# Clock-Gen.net
KiCad netlist of a schematic drawn in Altium Designer
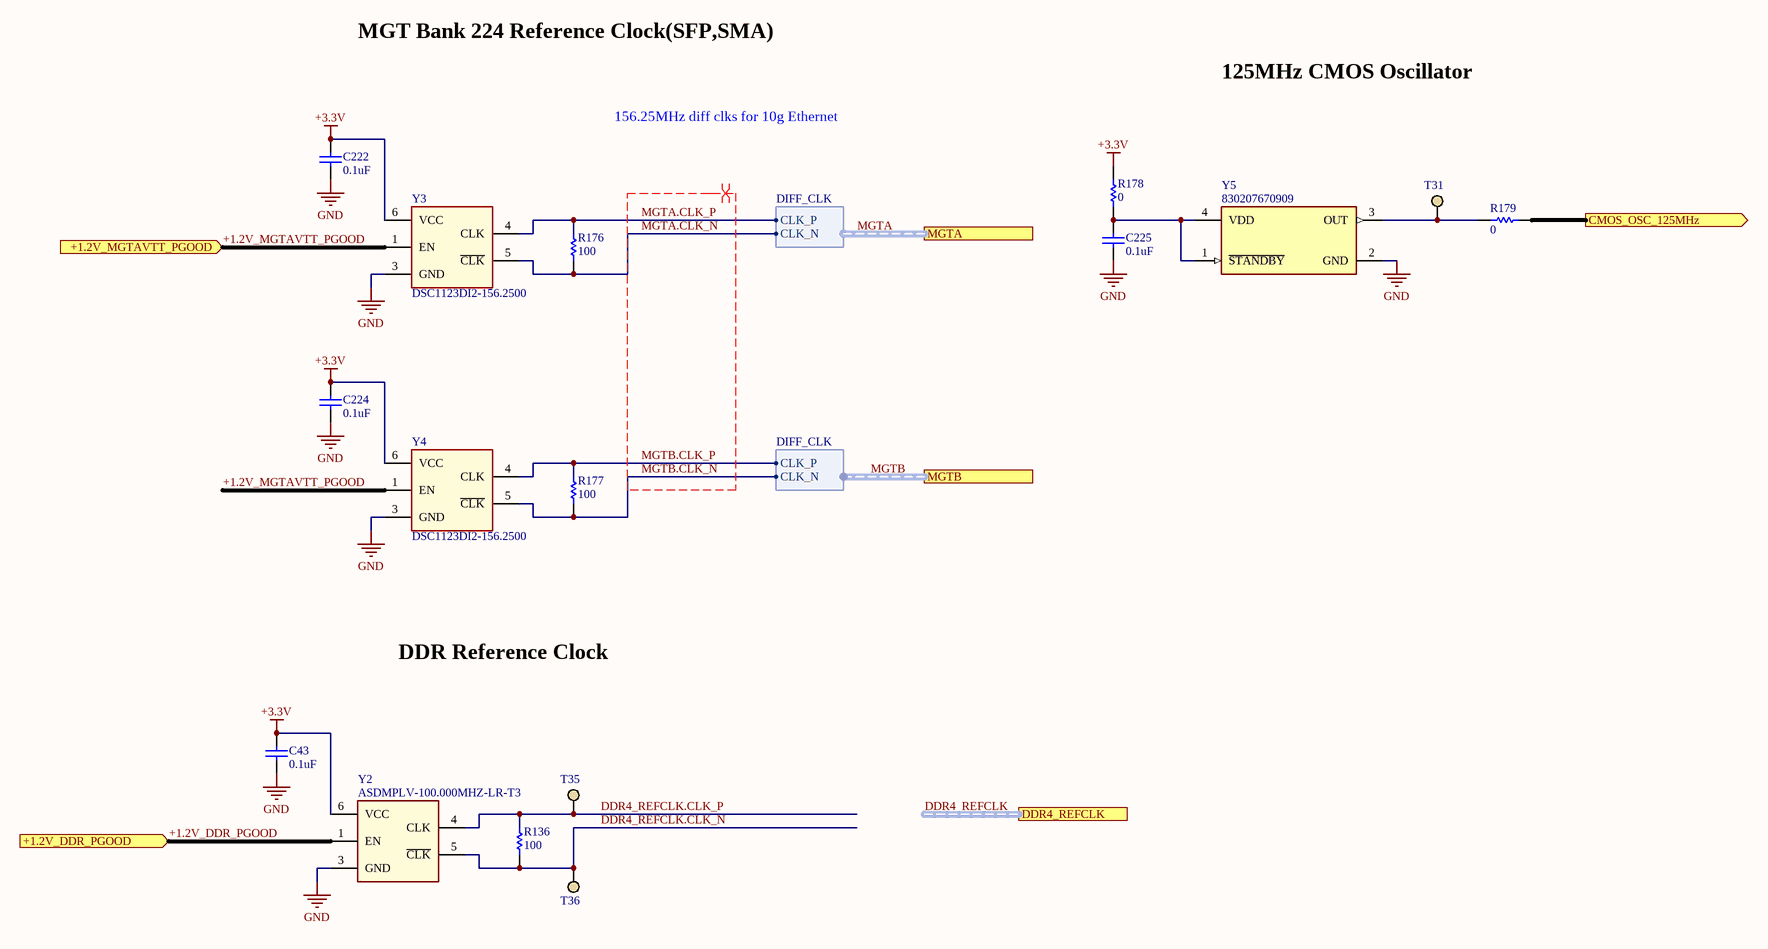
[diagram p0: Clock-Gen.SchDoc]

(export (version "E")
  (design (tool "Eeschema 10.0.6"))
  (components
    (comp (ref "C43")
      (value "0.1uF")
      (footprint "CAPC1005X55USR")
      (description "CAP CER 0.1UF 25V X5R 0402")
      (fields
        (field (name "MANUFACTURER PART NUMBER") "CL05A104KA5NNNC")
        (field (name "MANUFACTURER") "Samsung Electro-Mechanics")
      )
      (libsource (lib "Radar FPGA RF") (part "CAP CER 0.1UF 25V X5R 0402"))
    )
    (comp (ref "C222")
      (value "0.1uF")
      (footprint "CAPC1005X55USR")
      (description "CAP CER 0.1UF 25V X5R 0402")
      (fields
        (field (name "MANUFACTURER PART NUMBER") "CL05A104KA5NNNC")
        (field (name "MANUFACTURER") "Samsung Electro-Mechanics")
      )
      (libsource (lib "Radar FPGA RF") (part "CAP CER 0.1UF 25V X5R 0402"))
    )
    (comp (ref "C224")
      (value "0.1uF")
      (footprint "CAPC1005X55USR")
      (description "CAP CER 0.1UF 25V X5R 0402")
      (fields
        (field (name "MANUFACTURER PART NUMBER") "CL05A104KA5NNNC")
        (field (name "MANUFACTURER") "Samsung Electro-Mechanics")
      )
      (libsource (lib "Radar FPGA RF") (part "CAP CER 0.1UF 25V X5R 0402"))
    )
    (comp (ref "C225")
      (value "0.1uF")
      (footprint "CAPC1005X55USR")
      (description "CAP CER 0.1UF 25V X5R 0402")
      (fields
        (field (name "MANUFACTURER PART NUMBER") "CL05A104KA5NNNC")
        (field (name "MANUFACTURER") "Samsung Electro-Mechanics")
      )
      (libsource (lib "Radar FPGA RF") (part "CAP CER 0.1UF 25V X5R 0402"))
    )
    (comp (ref "R136")
      (value "100")
      (footprint "RESC1005X40USR")
      (description "RES 100 OHM 1% 1/16W 0402")
      (fields
        (field (name "MANUFACTURER") "YAGEO")
        (field (name "MANUFACTURER PART NUMBER") "RC0402FR-07100RL")
      )
      (libsource (lib "Radar FPGA RF") (part "RES 100 OHM 1% 1/16W 0402"))
    )
    (comp (ref "R176")
      (value "100")
      (footprint "RESC1005X40USR")
      (description "RES 100 OHM 1% 1/16W 0402")
      (fields
        (field (name "MANUFACTURER") "YAGEO")
        (field (name "MANUFACTURER PART NUMBER") "RC0402FR-07100RL")
      )
      (libsource (lib "Radar FPGA RF") (part "RES 100 OHM 1% 1/16W 0402"))
    )
    (comp (ref "R177")
      (value "100")
      (footprint "RESC1005X40USR")
      (description "RES 100 OHM 1% 1/16W 0402")
      (fields
        (field (name "MANUFACTURER") "YAGEO")
        (field (name "MANUFACTURER PART NUMBER") "RC0402FR-07100RL")
      )
      (libsource (lib "Radar FPGA RF") (part "RES 100 OHM 1% 1/16W 0402"))
    )
    (comp (ref "R178")
      (value "0")
      (footprint "RESC1005X40USR")
      (description "RES 0 OHM JUMPER 1/16W 0402")
      (fields
        (field (name "MANUFACTURER") "Yageo")
        (field (name "MANUFACTURER PART NUMBER") "RC0402JR-070RL")
      )
      (libsource (lib "Radar FPGA RF") (part "RES 0 OHM JUMPER 1/16W 0402"))
    )
    (comp (ref "R179")
      (value "0")
      (footprint "RESC1005X40USR")
      (description "RES 0 OHM JUMPER 1/16W 0402")
      (fields
        (field (name "MANUFACTURER") "Yageo")
        (field (name "MANUFACTURER PART NUMBER") "RC0402JR-070RL")
      )
      (libsource (lib "Radar FPGA RF") (part "RES 0 OHM JUMPER 1/16W 0402"))
    )
    (comp (ref "T31")
      (value "TP_S")
      (footprint "TP_SM_1MM")
      (description "test point")
      (libsource (lib "Radar FPGA RF") (part "Test point PAD"))
    )
    (comp (ref "T35")
      (value "TP_S")
      (footprint "TP_SM_1MM")
      (description "test point")
      (libsource (lib "Radar FPGA RF") (part "Test point PAD"))
    )
    (comp (ref "T36")
      (value "TP_S")
      (footprint "TP_SM_1MM")
      (description "test point")
      (libsource (lib "Radar FPGA RF") (part "Test point PAD"))
    )
    (comp (ref "Y2")
      (value "ASDMPLV-100.000MHZ-LR-T3")
      (footprint "6-SMD (2.50mm x 2.00mm)")
      (description "Oscillator MEMS 100MHz ±25ppm (Stability) LVDS 52% 2.5V/3.3V 6-Pin QFN SMD T/R")
      (fields (field (name "MANUFACTURER") "Abracon"))
      (libsource (lib "XEM8320") (part "ASDMPLV-100.000MHZ-LR-T3"))
    )
    (comp (ref "Y3")
      (value "DSC1123DI2-156.2500")
      (footprint "6-SMD (2.50mm x 2.00mm)")
      (description "MEMS Oscillator High Perf Single LVDS Output -40C-85C 25ppm")
      (fields (field (name "MANUFACTURER") "Microchip"))
      (libsource (lib "XEM8320") (part "DSC1123DI2-156.2500"))
    )
    (comp (ref "Y4")
      (value "DSC1123DI2-156.2500")
      (footprint "6-SMD (2.50mm x 2.00mm)")
      (description "MEMS Oscillator High Perf Single LVDS Output -40C-85C 25ppm")
      (fields (field (name "MANUFACTURER") "Microchip"))
      (libsource (lib "XEM8320") (part "DSC1123DI2-156.2500"))
    )
    (comp (ref "Y5")
      (value "830207670909")
      (footprint "XTAL_CX3225SA")
      (description "Xtal Osc Xo 125.0000MHZ Cmos")
      (fields (field (name "MANUFACTURER") "Wurth Electronics"))
      (libsource (lib "XEM8320") (part "830207670909"))
    )
  )
  (nets
    (net (code "4") (name "+3.3V") (class "Default")
      (node (ref "C222") (pin "1") (pinfunction "1_1") (pintype "passive"))
      (node (ref "C224") (pin "1") (pinfunction "1_1") (pintype "passive"))
      (node (ref "C43") (pin "1") (pinfunction "1_1") (pintype "passive"))
      (node (ref "R178") (pin "1") (pinfunction "1_1") (pintype "passive"))
      (node (ref "Y2") (pin "6") (pinfunction "VCC_6") (pintype "passive"))
      (node (ref "Y3") (pin "6") (pinfunction "VCC_6") (pintype "passive"))
      (node (ref "Y4") (pin "6") (pinfunction "VCC_6") (pintype "passive"))
    )
    (net (code "5") (name "/+1.2V_DDR_PGOOD") (class "Default")
      (node (ref "Y2") (pin "1") (pinfunction "EN_1") (pintype "passive"))
    )
    (net (code "6") (name "/+1.2V_MGTAVTT_PGOOD") (class "Default")
      (node (ref "Y3") (pin "1") (pinfunction "EN_1") (pintype "passive"))
      (node (ref "Y4") (pin "1") (pinfunction "EN_1") (pintype "passive"))
    )
    (net (code "7") (name "/CMOS_OSC_125MHz") (class "Default")
      (node (ref "R179") (pin "2") (pinfunction "2_2") (pintype "passive"))
    )
    (net (code "8") (name "/DDR4_REFCLK.CLK_N") (class "Default")
      (node (ref "R136") (pin "1") (pinfunction "1_1") (pintype "passive"))
      (node (ref "T36") (pin "1") (pintype "passive"))
      (node (ref "Y2") (pin "5") (pinfunction "~{CLK}_5") (pintype "passive"))
    )
    (net (code "9") (name "/DDR4_REFCLK.CLK_P") (class "Default")
      (node (ref "R136") (pin "2") (pinfunction "2_2") (pintype "passive"))
      (node (ref "T35") (pin "1") (pintype "passive"))
      (node (ref "Y2") (pin "4") (pinfunction "CLK_4") (pintype "passive"))
    )
    (net (code "10") (name "/MGTA.CLK_N") (class "Default")
      (node (ref "R176") (pin "1") (pinfunction "1_1") (pintype "passive"))
      (node (ref "Y3") (pin "5") (pinfunction "~{CLK}_5") (pintype "passive"))
    )
    (net (code "11") (name "/MGTA.CLK_P") (class "Default")
      (node (ref "R176") (pin "2") (pinfunction "2_2") (pintype "passive"))
      (node (ref "Y3") (pin "4") (pinfunction "CLK_4") (pintype "passive"))
    )
    (net (code "13") (name "/MGTB.CLK_N") (class "Default")
      (node (ref "R177") (pin "1") (pinfunction "1_1") (pintype "passive"))
      (node (ref "Y4") (pin "5") (pinfunction "~{CLK}_5") (pintype "passive"))
    )
    (net (code "14") (name "/MGTB.CLK_P") (class "Default")
      (node (ref "R177") (pin "2") (pinfunction "2_2") (pintype "passive"))
      (node (ref "Y4") (pin "4") (pinfunction "CLK_4") (pintype "passive"))
    )
    (net (code "17") (name "GND") (class "Default")
      (node (ref "C222") (pin "2") (pinfunction "2_2") (pintype "passive"))
      (node (ref "C224") (pin "2") (pinfunction "2_2") (pintype "passive"))
      (node (ref "C225") (pin "2") (pinfunction "2_2") (pintype "passive"))
      (node (ref "C43") (pin "2") (pinfunction "2_2") (pintype "passive"))
      (node (ref "Y2") (pin "3") (pinfunction "GND_3") (pintype "passive"))
      (node (ref "Y3") (pin "3") (pinfunction "GND_3") (pintype "passive"))
      (node (ref "Y4") (pin "3") (pinfunction "GND_3") (pintype "passive"))
      (node (ref "Y5") (pin "2") (pinfunction "GND_2") (pintype "power_in"))
    )
    (net (code "18") (name "Net-(Y5-OUT)") (class "Default")
      (node (ref "R179") (pin "1") (pinfunction "1_1") (pintype "passive"))
      (node (ref "T31") (pin "1") (pintype "passive"))
      (node (ref "Y5") (pin "3") (pinfunction "OUT_3") (pintype "output"))
    )
    (net (code "19") (name "Net-(Y5-VDD)") (class "Default")
      (node (ref "C225") (pin "1") (pinfunction "1_1") (pintype "passive"))
      (node (ref "R178") (pin "2") (pinfunction "2_2") (pintype "passive"))
      (node (ref "Y5") (pin "1") (pinfunction "~{STANDBY}_1") (pintype "input"))
      (node (ref "Y5") (pin "4") (pinfunction "VDD_4") (pintype "power_in"))
    )
  )
)
